# Preamp.net
KiCad netlist of a schematic drawn in EAGLE
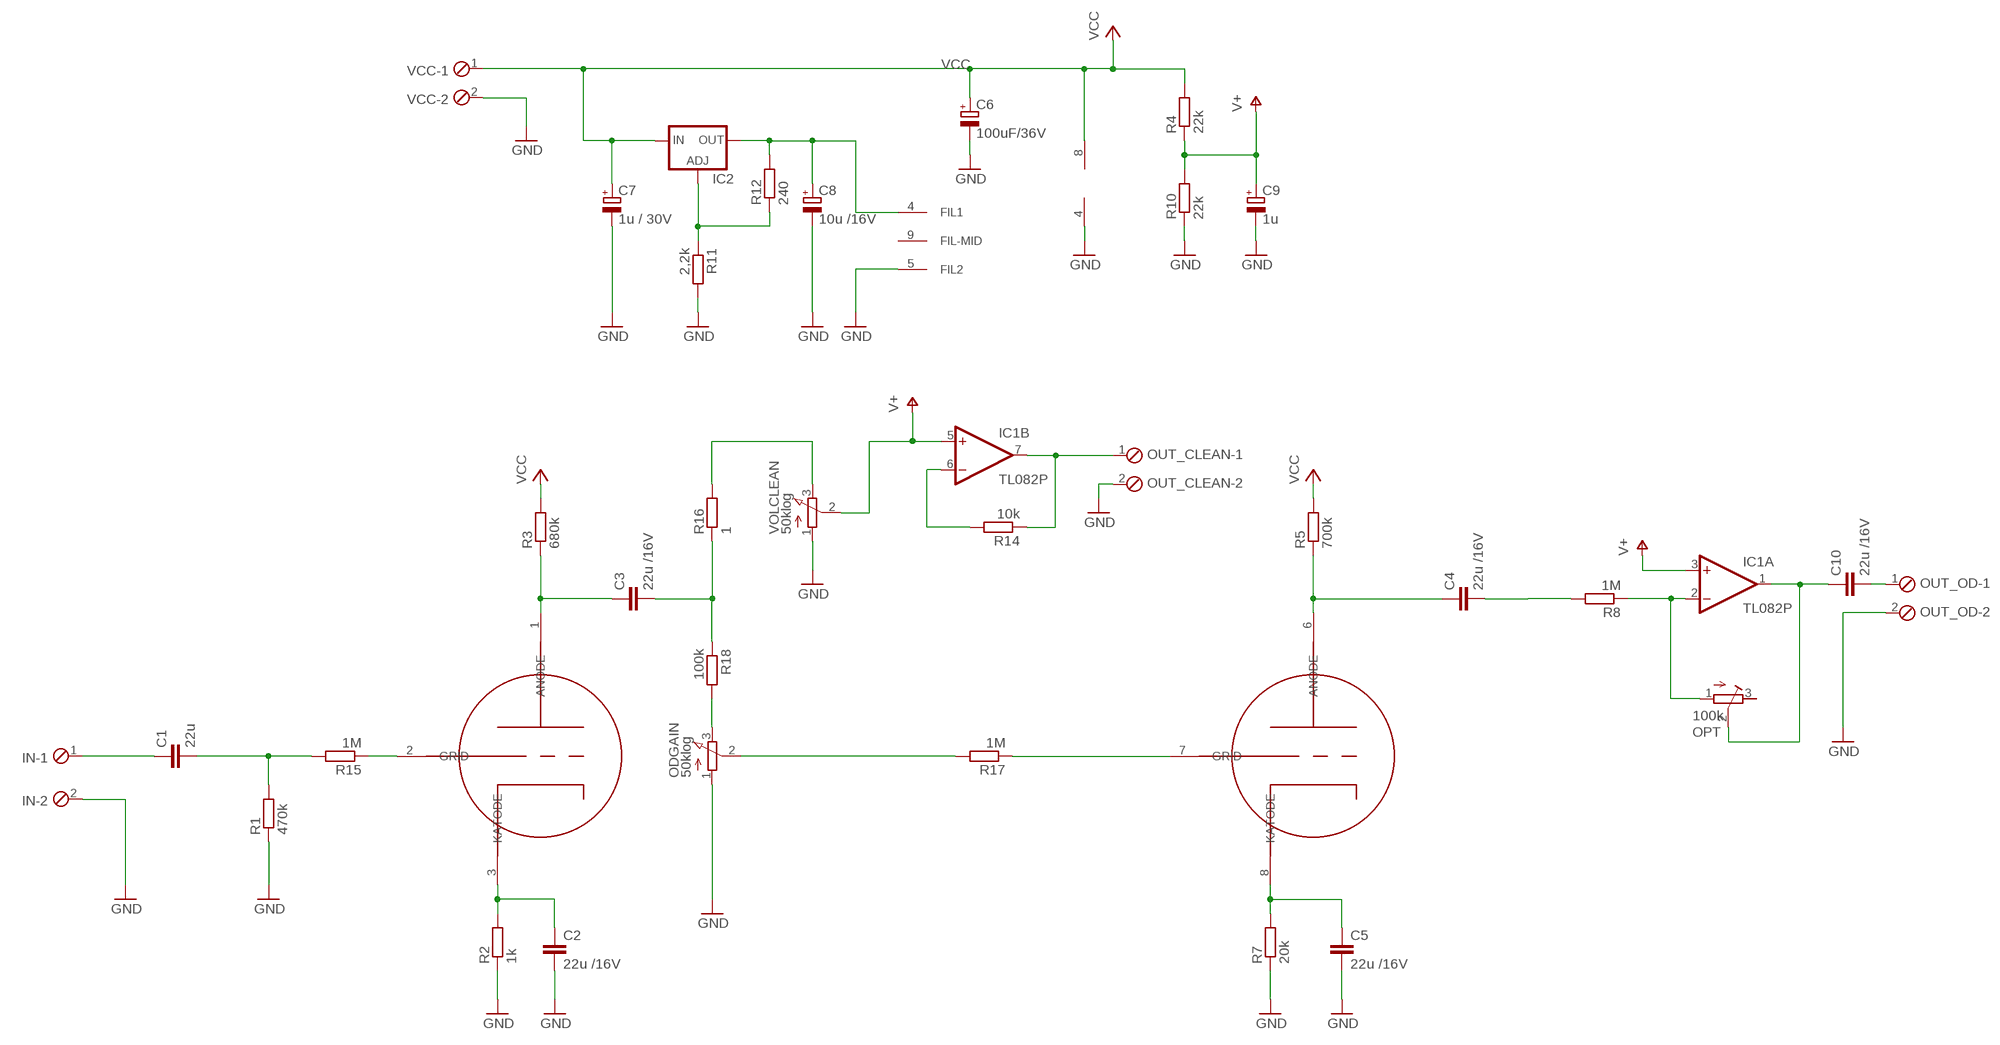
[diagram p0: schematic, sheet 1]

(export (version "E")
  (design (tool "Eeschema 10.0.6"))
  (components
    (comp (ref "C1")
      (value "22u")
      (footprint "eagle-import:C050-030X075")
      (libsource (lib "eagle-import") (part "C-EU050-030X075"))
    )
    (comp (ref "C2")
      (value "22u /16V")
      (footprint "eagle-import:C050-030X075")
      (libsource (lib "eagle-import") (part "C-EU050-030X075"))
    )
    (comp (ref "C3")
      (value "22u /16V")
      (footprint "eagle-import:C050-030X075")
      (libsource (lib "eagle-import") (part "C-EU050-030X075"))
    )
    (comp (ref "C4")
      (value "22u /16V")
      (footprint "eagle-import:C050-030X075")
      (libsource (lib "eagle-import") (part "C-EU050-030X075"))
    )
    (comp (ref "C5")
      (value "22u /16V")
      (footprint "eagle-import:C050-030X075")
      (libsource (lib "eagle-import") (part "C-EU050-030X075"))
    )
    (comp (ref "C6")
      (value "100uF/36V")
      (footprint "eagle-import:E2,5-5")
      (libsource (lib "eagle-import") (part "CPOL-EUE2.5-5"))
    )
    (comp (ref "C7")
      (value "1u / 30V")
      (footprint "eagle-import:E2,5-5")
      (libsource (lib "eagle-import") (part "CPOL-EUE2.5-5"))
    )
    (comp (ref "C8")
      (value "10u /16V")
      (footprint "eagle-import:E2,5-5")
      (libsource (lib "eagle-import") (part "CPOL-EUE2.5-5"))
    )
    (comp (ref "C9")
      (value "1u")
      (footprint "eagle-import:E2,5-5")
      (libsource (lib "eagle-import") (part "CPOL-EUE2.5-5"))
    )
    (comp (ref "C10")
      (value "22u /16V")
      (footprint "eagle-import:C050-030X075")
      (libsource (lib "eagle-import") (part "C-EU050-030X075"))
    )
    (comp (ref "IC1")
      (value "TL082P")
      (footprint "eagle-import:DIL08")
      (libsource (lib "eagle-import") (part "TL082P"))
    )
    (comp (ref "IC2")
      (value "LM317TS")
      (footprint "eagle-import:317TS")
      (libsource (lib "eagle-import") (part "LM317TS"))
    )
    (comp (ref "IN")
      (value "MPT2")
      (footprint "eagle-import:2POL254")
      (libsource (lib "eagle-import") (part "MPT2"))
    )
    (comp (ref "ODGAIN")
      (value "50klog")
      (footprint "eagle-import:3RP_1610N")
      (libsource (lib "eagle-import") (part "3RP/1610N"))
    )
    (comp (ref "OPT")
      (value "100k")
      (footprint "eagle-import:RTRIM74W")
      (libsource (lib "eagle-import") (part "R-TRIMM74W"))
    )
    (comp (ref "OUT_CLEAN")
      (value "MPT2")
      (footprint "eagle-import:2POL254")
      (libsource (lib "eagle-import") (part "MPT2"))
    )
    (comp (ref "OUT_OD")
      (value "MPT2")
      (footprint "eagle-import:2POL254")
      (libsource (lib "eagle-import") (part "MPT2"))
    )
    (comp (ref "R1")
      (value "470k")
      (footprint "eagle-import:0207_12")
      (libsource (lib "eagle-import") (part "R-EU_0207/12"))
    )
    (comp (ref "R2")
      (value "1k")
      (footprint "eagle-import:0207_12")
      (libsource (lib "eagle-import") (part "R-EU_0207/12"))
    )
    (comp (ref "R3")
      (value "680k")
      (footprint "eagle-import:0207_12")
      (libsource (lib "eagle-import") (part "R-EU_0207/12"))
    )
    (comp (ref "R4")
      (value "22k")
      (footprint "eagle-import:0207_12")
      (libsource (lib "eagle-import") (part "R-EU_0207/12"))
    )
    (comp (ref "R5")
      (value "700k")
      (footprint "eagle-import:0207_12")
      (libsource (lib "eagle-import") (part "R-EU_0207/12"))
    )
    (comp (ref "R7")
      (value "20k")
      (footprint "eagle-import:0207_10")
      (libsource (lib "eagle-import") (part "R-EU_0207/10"))
    )
    (comp (ref "R8")
      (value "1M")
      (footprint "eagle-import:0207_12")
      (libsource (lib "eagle-import") (part "R-EU_0207/12"))
    )
    (comp (ref "R10")
      (value "22k")
      (footprint "eagle-import:0207_12")
      (libsource (lib "eagle-import") (part "R-EU_0207/12"))
    )
    (comp (ref "R11")
      (value "2,2k")
      (footprint "eagle-import:0207_12")
      (libsource (lib "eagle-import") (part "R-EU_0207/12"))
    )
    (comp (ref "R12")
      (value "240")
      (footprint "eagle-import:0207_12")
      (libsource (lib "eagle-import") (part "R-EU_0207/12"))
    )
    (comp (ref "R14")
      (value "10k")
      (footprint "eagle-import:0204_7")
      (libsource (lib "eagle-import") (part "R-EU_0204/7"))
    )
    (comp (ref "R15")
      (value "1M")
      (footprint "eagle-import:0207_12")
      (libsource (lib "eagle-import") (part "R-EU_0207/12"))
    )
    (comp (ref "R16")
      (value "1")
      (footprint "eagle-import:0207_12")
      (libsource (lib "eagle-import") (part "R-EU_0207/12"))
    )
    (comp (ref "R17")
      (value "1M")
      (footprint "eagle-import:0207_12")
      (libsource (lib "eagle-import") (part "R-EU_0207/12"))
    )
    (comp (ref "R18")
      (value "100k")
      (footprint "eagle-import:0207_12")
      (libsource (lib "eagle-import") (part "R-EU_0207/12"))
    )
    (comp (ref "U$1")
      (value "12AX7")
      (footprint "eagle-import:12AX7")
      (libsource (lib "eagle-import") (part "12AX7"))
    )
    (comp (ref "VCC")
      (value "MPT2")
      (footprint "eagle-import:2POL254")
      (libsource (lib "eagle-import") (part "MPT2"))
    )
    (comp (ref "VOLCLEAN")
      (value "50klog")
      (footprint "eagle-import:3RP_1610N")
      (libsource (lib "eagle-import") (part "3RP/1610N"))
    )
  )
  (nets
    (net (code "1") (name "GND") (class "Default")
      (node (ref "C2") (pin "2") (pinfunction "2_2") (pintype "passive"))
      (node (ref "C5") (pin "2") (pinfunction "2_2") (pintype "passive"))
      (node (ref "C6") (pin "-") (pinfunction "-_-") (pintype "passive"))
      (node (ref "C7") (pin "-") (pinfunction "-_-") (pintype "passive"))
      (node (ref "C8") (pin "-") (pinfunction "-_-") (pintype "passive"))
      (node (ref "C9") (pin "-") (pinfunction "-_-") (pintype "passive"))
      (node (ref "IC1") (pin "4") (pinfunction "V-_4") (pintype "power_in"))
      (node (ref "IN") (pin "2") (pinfunction "1_2") (pintype "passive"))
      (node (ref "ODGAIN") (pin "1") (pinfunction "A_1") (pintype "passive"))
      (node (ref "OUT_CLEAN") (pin "2") (pinfunction "1_2") (pintype "passive"))
      (node (ref "OUT_OD") (pin "2") (pinfunction "1_2") (pintype "passive"))
      (node (ref "R1") (pin "1") (pinfunction "1_1") (pintype "passive"))
      (node (ref "R10") (pin "1") (pinfunction "1_1") (pintype "passive"))
      (node (ref "R11") (pin "2") (pinfunction "2_2") (pintype "passive"))
      (node (ref "R2") (pin "1") (pinfunction "1_1") (pintype "passive"))
      (node (ref "R7") (pin "1") (pinfunction "1_1") (pintype "passive"))
      (node (ref "U$1") (pin "5") (pinfunction "FIL2_5") (pintype "bidirectional"))
      (node (ref "VCC") (pin "2") (pinfunction "1_2") (pintype "passive"))
      (node (ref "VOLCLEAN") (pin "1") (pinfunction "A_1") (pintype "passive"))
    )
    (net (code "2") (name "Net-(C1-Pad1)") (class "Default")
      (node (ref "C1") (pin "1") (pinfunction "1_1") (pintype "passive"))
      (node (ref "IN") (pin "1") (pinfunction "1_1") (pintype "passive"))
    )
    (net (code "3") (name "Net-(C1-Pad2)") (class "Default")
      (node (ref "C1") (pin "2") (pinfunction "2_2") (pintype "passive"))
      (node (ref "R1") (pin "2") (pinfunction "2_2") (pintype "passive"))
      (node (ref "R15") (pin "2") (pinfunction "2_2") (pintype "passive"))
    )
    (net (code "4") (name "Net-(C3-Pad2)") (class "Default")
      (node (ref "C3") (pin "2") (pinfunction "2_2") (pintype "passive"))
      (node (ref "R16") (pin "1") (pinfunction "1_1") (pintype "passive"))
      (node (ref "R18") (pin "1") (pinfunction "1_1") (pintype "passive"))
    )
    (net (code "5") (name "Net-(C4-Pad2)") (class "Default")
      (node (ref "C4") (pin "2") (pinfunction "2_2") (pintype "passive"))
      (node (ref "R8") (pin "2") (pinfunction "2_2") (pintype "passive"))
    )
    (net (code "6") (name "Net-(C10-Pad2)") (class "Default")
      (node (ref "C10") (pin "2") (pinfunction "2_2") (pintype "passive"))
      (node (ref "OUT_OD") (pin "1") (pinfunction "1_1") (pintype "passive"))
    )
    (net (code "7") (name "Net-(IC1A--IN)") (class "Default")
      (node (ref "IC1") (pin "2") (pinfunction "-IN_2") (pintype "input"))
      (node (ref "OPT") (pin "1") (pinfunction "A_1") (pintype "passive"))
      (node (ref "R8") (pin "1") (pinfunction "1_1") (pintype "passive"))
    )
    (net (code "8") (name "Net-(IC1A-OUT)") (class "Default")
      (node (ref "C10") (pin "1") (pinfunction "1_1") (pintype "passive"))
      (node (ref "IC1") (pin "1") (pinfunction "OUT_1") (pintype "output"))
      (node (ref "OPT") (pin "2") (pinfunction "S_2") (pintype "passive"))
    )
    (net (code "9") (name "Net-(IC1B--IN)") (class "Default")
      (node (ref "IC1") (pin "6") (pinfunction "-IN_6") (pintype "input"))
      (node (ref "R14") (pin "2") (pinfunction "2_2") (pintype "passive"))
    )
    (net (code "10") (name "Net-(IC1B-OUT)") (class "Default")
      (node (ref "IC1") (pin "7") (pinfunction "OUT_7") (pintype "output"))
      (node (ref "OUT_CLEAN") (pin "1") (pinfunction "1_1") (pintype "passive"))
      (node (ref "R14") (pin "1") (pinfunction "1_1") (pintype "passive"))
    )
    (net (code "11") (name "Net-(IC2-ADJ)") (class "Default")
      (node (ref "IC2") (pin "1") (pinfunction "ADJ_1") (pintype "input"))
      (node (ref "R11") (pin "1") (pinfunction "1_1") (pintype "passive"))
      (node (ref "R12") (pin "1") (pinfunction "1_1") (pintype "passive"))
    )
    (net (code "12") (name "Net-(IC2-OUT)") (class "Default")
      (node (ref "C8") (pin "+") (pinfunction "+_+") (pintype "passive"))
      (node (ref "IC2") (pin "2") (pinfunction "OUT_2") (pintype "passive"))
      (node (ref "R12") (pin "2") (pinfunction "2_2") (pintype "passive"))
      (node (ref "U$1") (pin "4") (pinfunction "FIL1_4") (pintype "bidirectional"))
    )
    (net (code "13") (name "Net-(ODGAIN-E)") (class "Default")
      (node (ref "ODGAIN") (pin "3") (pinfunction "E_3") (pintype "passive"))
      (node (ref "R18") (pin "2") (pinfunction "2_2") (pintype "passive"))
    )
    (net (code "14") (name "Net-(ODGAIN-S)") (class "Default")
      (node (ref "ODGAIN") (pin "2") (pinfunction "S_2") (pintype "passive"))
      (node (ref "R17") (pin "2") (pinfunction "2_2") (pintype "passive"))
    )
    (net (code "15") (name "Net-(U$1A-ANODE)") (class "Default")
      (node (ref "C4") (pin "1") (pinfunction "1_1") (pintype "passive"))
      (node (ref "R5") (pin "1") (pinfunction "1_1") (pintype "passive"))
      (node (ref "U$1") (pin "6") (pinfunction "ANODE_6") (pintype "bidirectional"))
    )
    (net (code "16") (name "Net-(U$1A-GRID)") (class "Default")
      (node (ref "R17") (pin "1") (pinfunction "1_1") (pintype "passive"))
      (node (ref "U$1") (pin "7") (pinfunction "GRID_7") (pintype "bidirectional"))
    )
    (net (code "17") (name "Net-(U$1A-KATODE)") (class "Default")
      (node (ref "C5") (pin "1") (pinfunction "1_1") (pintype "passive"))
      (node (ref "R7") (pin "2") (pinfunction "2_2") (pintype "passive"))
      (node (ref "U$1") (pin "8") (pinfunction "KATODE_8") (pintype "bidirectional"))
    )
    (net (code "18") (name "Net-(U$1B-ANODE)") (class "Default")
      (node (ref "C3") (pin "1") (pinfunction "1_1") (pintype "passive"))
      (node (ref "R3") (pin "1") (pinfunction "1_1") (pintype "passive"))
      (node (ref "U$1") (pin "1") (pinfunction "ANODE_1") (pintype "bidirectional"))
    )
    (net (code "19") (name "Net-(U$1B-GRID)") (class "Default")
      (node (ref "R15") (pin "1") (pinfunction "1_1") (pintype "passive"))
      (node (ref "U$1") (pin "2") (pinfunction "GRID_2") (pintype "bidirectional"))
    )
    (net (code "20") (name "Net-(U$1B-KATODE)") (class "Default")
      (node (ref "C2") (pin "1") (pinfunction "1_1") (pintype "passive"))
      (node (ref "R2") (pin "2") (pinfunction "2_2") (pintype "passive"))
      (node (ref "U$1") (pin "3") (pinfunction "KATODE_3") (pintype "bidirectional"))
    )
    (net (code "21") (name "Net-(VOLCLEAN-E)") (class "Default")
      (node (ref "R16") (pin "2") (pinfunction "2_2") (pintype "passive"))
      (node (ref "VOLCLEAN") (pin "3") (pinfunction "E_3") (pintype "passive"))
    )
    (net (code "22") (name "V+") (class "Default")
      (node (ref "C9") (pin "+") (pinfunction "+_+") (pintype "passive"))
      (node (ref "IC1") (pin "3") (pinfunction "+IN_3") (pintype "input"))
      (node (ref "IC1") (pin "5") (pinfunction "+IN_5") (pintype "input"))
      (node (ref "R10") (pin "2") (pinfunction "2_2") (pintype "passive"))
      (node (ref "R4") (pin "1") (pinfunction "1_1") (pintype "passive"))
      (node (ref "VOLCLEAN") (pin "2") (pinfunction "S_2") (pintype "passive"))
    )
    (net (code "23") (name "VCC") (class "Default")
      (node (ref "C6") (pin "+") (pinfunction "+_+") (pintype "passive"))
      (node (ref "C7") (pin "+") (pinfunction "+_+") (pintype "passive"))
      (node (ref "IC1") (pin "8") (pinfunction "V+_8") (pintype "power_in"))
      (node (ref "IC2") (pin "3") (pinfunction "IN_3") (pintype "input"))
      (node (ref "R3") (pin "2") (pinfunction "2_2") (pintype "passive"))
      (node (ref "R4") (pin "2") (pinfunction "2_2") (pintype "passive"))
      (node (ref "R5") (pin "2") (pinfunction "2_2") (pintype "passive"))
      (node (ref "VCC") (pin "1") (pinfunction "1_1") (pintype "passive"))
    )
    (net (code "24") (name "unconnected-(OPT-E-Pad3)") (class "Default")
      (node (ref "OPT") (pin "3") (pinfunction "E_3") (pintype "passive"))
    )
    (net (code "25") (name "unconnected-(U$1C-FIL-MID-Pad9)") (class "Default")
      (node (ref "U$1") (pin "9") (pinfunction "FIL-MID_9") (pintype "bidirectional"))
    )
  )
)
